# v1.net
KiCad netlist of a schematic drawn in EAGLE
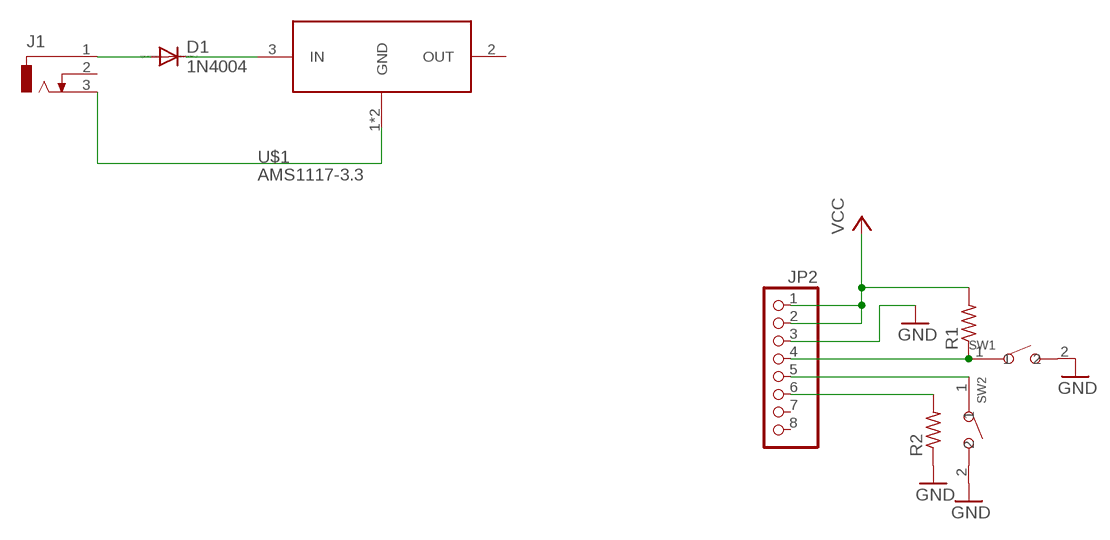
[diagram p0: schematic, sheet 1]

(export (version "E")
  (design (tool "Eeschema 10.0.6"))
  (components
    (comp (ref "D1")
      (value "1N4004")
      (footprint "eagle-import:DO41-10")
      (libsource (lib "eagle-import") (part "1N4004"))
    )
    (comp (ref "J1")
      (value "DCJ0303")
      (footprint "eagle-import:DCJ0303")
      (libsource (lib "eagle-import") (part "DCJ0303"))
    )
    (comp (ref "JP2")
      (value "PINHD-1X8")
      (footprint "eagle-import:1X08")
      (libsource (lib "eagle-import") (part "PINHD-1X8"))
    )
    (comp (ref "R1")
      (value "R-US_0204/5")
      (footprint "eagle-import:0204_5")
      (libsource (lib "eagle-import") (part "R-US_0204/5"))
    )
    (comp (ref "R2")
      (value "R-US_0204/5")
      (footprint "eagle-import:0204_5")
      (libsource (lib "eagle-import") (part "R-US_0204/5"))
    )
    (comp (ref "SW1")
      (value "DIP-BUTTON(2P-6.0X3.0X4.3MM)-TS-1101F")
      (footprint "eagle-import:SW2-5.0-6.0X3.0X4.3MM")
      (libsource (lib "eagle-import") (part "DIP-BUTTON(2P-6.0X3.0X4.3MM)-TS-1101F"))
    )
    (comp (ref "SW2")
      (value "DIP-BUTTON(2P-6.0X3.0X4.3MM)-TS-1101F")
      (footprint "eagle-import:SW2-5.0-6.0X3.0X4.3MM")
      (libsource (lib "eagle-import") (part "DIP-BUTTON(2P-6.0X3.0X4.3MM)-TS-1101F"))
    )
    (comp (ref "U$1")
      (value "AMS1117-3.3")
      (footprint "eagle-import:SOT-223")
      (libsource (lib "eagle-import") (part "AMS1117-3.3"))
    )
  )
  (nets
    (net (code "1") (name "GND") (class "Default")
      (node (ref "JP2") (pin "3") (pinfunction "3_3") (pintype "passive"))
      (node (ref "R2") (pin "1") (pinfunction "1_1") (pintype "passive"))
      (node (ref "SW1") (pin "2") (pinfunction "2_2") (pintype "bidirectional"))
      (node (ref "SW2") (pin "2") (pinfunction "2_2") (pintype "bidirectional"))
    )
    (net (code "2") (name "Net-(D1-PadA)") (class "Default")
      (node (ref "D1") (pin "A") (pinfunction "A_A") (pintype "passive"))
      (node (ref "J1") (pin "1") (pinfunction "1_1") (pintype "passive"))
    )
    (net (code "3") (name "Net-(J1-Pad3)") (class "Default")
      (node (ref "J1") (pin "3") (pinfunction "3_3") (pintype "passive"))
      (node (ref "U$1") (pin "1") (pinfunction "GND_1") (pintype "passive"))
      (node (ref "U$1") (pin "4") (pinfunction "GND_4") (pintype "passive"))
    )
    (net (code "4") (name "Net-(JP2-Pad4)") (class "Default")
      (node (ref "JP2") (pin "4") (pinfunction "4_4") (pintype "passive"))
      (node (ref "R1") (pin "1") (pinfunction "1_1") (pintype "passive"))
      (node (ref "SW1") (pin "1") (pinfunction "1_1") (pintype "bidirectional"))
    )
    (net (code "5") (name "Net-(JP2-Pad5)") (class "Default")
      (node (ref "JP2") (pin "5") (pinfunction "5_5") (pintype "passive"))
      (node (ref "SW2") (pin "1") (pinfunction "1_1") (pintype "bidirectional"))
    )
    (net (code "6") (name "Net-(JP2-Pad6)") (class "Default")
      (node (ref "JP2") (pin "6") (pinfunction "6_6") (pintype "passive"))
      (node (ref "R2") (pin "2") (pinfunction "2_2") (pintype "passive"))
    )
    (net (code "7") (name "Net-(U$1-IN)") (class "Default")
      (node (ref "D1") (pin "C") (pinfunction "C_C") (pintype "passive"))
      (node (ref "U$1") (pin "3") (pinfunction "IN_3") (pintype "input"))
    )
    (net (code "8") (name "VCC") (class "Default")
      (node (ref "JP2") (pin "1") (pinfunction "1_1") (pintype "passive"))
      (node (ref "JP2") (pin "2") (pinfunction "2_2") (pintype "passive"))
      (node (ref "R1") (pin "2") (pinfunction "2_2") (pintype "passive"))
    )
    (net (code "9") (name "unconnected-(J1-Pad2)") (class "Default")
      (node (ref "J1") (pin "2") (pinfunction "2_2") (pintype "passive"))
    )
    (net (code "10") (name "unconnected-(JP2-Pad7)") (class "Default")
      (node (ref "JP2") (pin "7") (pinfunction "7_7") (pintype "passive"))
    )
    (net (code "11") (name "unconnected-(JP2-Pad8)") (class "Default")
      (node (ref "JP2") (pin "8") (pinfunction "8_8") (pintype "passive"))
    )
    (net (code "12") (name "unconnected-(U$1-OUT-Pad2)") (class "Default")
      (node (ref "U$1") (pin "2") (pinfunction "OUT_2") (pintype "output"))
    )
  )
)
